# test_instrumentation_amplifier.net
KiCad netlist of a schematic drawn in EAGLE
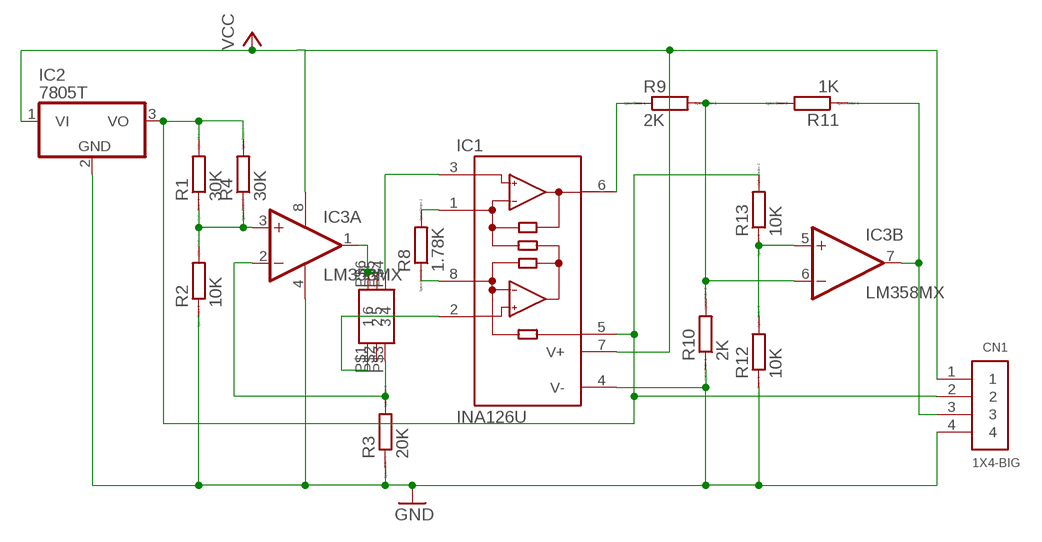
[diagram p0: schematic, sheet 1]

(export (version "E")
  (design (tool "Eeschema 10.0.6"))
  (components
    (comp (ref "CN1")
      (value "1X4-BIG")
      (footprint "eagle-import:1X04-BIG")
      (libsource (lib "eagle-import") (part "1X4-BIG"))
    )
    (comp (ref "IC1")
      (value "INA126U")
      (footprint "eagle-import:SO08")
      (fields (field (name "MF") "Texas Instruments") (field (name "MP") "INA126"))
      (libsource (lib "eagle-import") (part "INA126U"))
    )
    (comp (ref "IC2")
      (value "7805T")
      (footprint "eagle-import:TO220H")
      (fields (field (name "SPICEPREFIX") "X"))
      (libsource (lib "eagle-import") (part "78T05"))
    )
    (comp (ref "IC3")
      (value "LM358MX")
      (footprint "eagle-import:SO08")
      (libsource (lib "eagle-import") (part "LM358MX"))
    )
    (comp (ref "R1")
      (value "30K")
      (footprint "eagle-import:0207_10")
      (libsource (lib "eagle-import") (part "R0207/10"))
    )
    (comp (ref "R2")
      (value "10K")
      (footprint "eagle-import:0207_10")
      (libsource (lib "eagle-import") (part "R0207/10"))
    )
    (comp (ref "R3")
      (value "20K")
      (footprint "eagle-import:0207_10")
      (libsource (lib "eagle-import") (part "R0207/10"))
    )
    (comp (ref "R4")
      (value "30K")
      (footprint "eagle-import:0207_10")
      (libsource (lib "eagle-import") (part "R0207/10"))
    )
    (comp (ref "R8")
      (value "1.78K")
      (footprint "eagle-import:0207_10")
      (libsource (lib "eagle-import") (part "R0207/10"))
    )
    (comp (ref "R9")
      (value "2K")
      (footprint "eagle-import:0207_10")
      (libsource (lib "eagle-import") (part "R0207/10"))
    )
    (comp (ref "R10")
      (value "2K")
      (footprint "eagle-import:0207_10")
      (libsource (lib "eagle-import") (part "R0207/10"))
    )
    (comp (ref "R11")
      (value "1K")
      (footprint "eagle-import:0207_10")
      (libsource (lib "eagle-import") (part "R0207/10"))
    )
    (comp (ref "R12")
      (value "10K")
      (footprint "eagle-import:0207_10")
      (libsource (lib "eagle-import") (part "R0207/10"))
    )
    (comp (ref "R13")
      (value "10K")
      (footprint "eagle-import:0207_10")
      (libsource (lib "eagle-import") (part "R0207/10"))
    )
    (comp (ref "U$1")
      (value "2SMPP-03")
      (footprint "eagle-import:2SMPP-03")
      (libsource (lib "eagle-import") (part "2SMPP-03"))
    )
  )
  (nets
    (net (code "1") (name "GND") (class "Default")
      (node (ref "CN1") (pin "4") (pinfunction "4_4") (pintype "bidirectional"))
      (node (ref "IC1") (pin "4") (pinfunction "V-_4") (pintype "power_in"))
      (node (ref "IC2") (pin "2") (pinfunction "GND_2") (pintype "passive"))
      (node (ref "IC3") (pin "4") (pinfunction "V-_4") (pintype "power_in"))
      (node (ref "R10") (pin "1") (pinfunction "1_1") (pintype "passive"))
      (node (ref "R12") (pin "1") (pinfunction "1_1") (pintype "passive"))
      (node (ref "R2") (pin "1") (pinfunction "1_1") (pintype "passive"))
      (node (ref "R3") (pin "1") (pinfunction "1_1") (pintype "passive"))
    )
    (net (code "2") (name "Net-(IC1-+IN)") (class "Default")
      (node (ref "IC1") (pin "3") (pinfunction "+IN_3") (pintype "input"))
      (node (ref "U$1") (pin "P$4") (pinfunction "4_P$4") (pintype "bidirectional"))
    )
    (net (code "3") (name "Net-(IC1--IN)") (class "Default")
      (node (ref "IC1") (pin "2") (pinfunction "-IN_2") (pintype "input"))
      (node (ref "U$1") (pin "P$1") (pinfunction "1_P$1") (pintype "bidirectional"))
    )
    (net (code "4") (name "Net-(IC1-OUT)") (class "Default")
      (node (ref "IC1") (pin "6") (pinfunction "OUT_6") (pintype "output"))
      (node (ref "R9") (pin "1") (pinfunction "1_1") (pintype "passive"))
    )
    (net (code "5") (name "Net-(IC1-REF)") (class "Default")
      (node (ref "CN1") (pin "2") (pinfunction "2_2") (pintype "bidirectional"))
      (node (ref "IC1") (pin "5") (pinfunction "REF_5") (pintype "passive"))
      (node (ref "IC2") (pin "3") (pinfunction "VO_3") (pintype "passive"))
      (node (ref "R1") (pin "2") (pinfunction "2_2") (pintype "passive"))
      (node (ref "R13") (pin "2") (pinfunction "2_2") (pintype "passive"))
      (node (ref "R4") (pin "2") (pinfunction "2_2") (pintype "passive"))
    )
    (net (code "6") (name "Net-(IC1-RG-Pad1)") (class "Default")
      (node (ref "IC1") (pin "1") (pinfunction "RG_1") (pintype "passive"))
      (node (ref "R8") (pin "2") (pinfunction "2_2") (pintype "passive"))
    )
    (net (code "7") (name "Net-(IC1-RG-Pad8)") (class "Default")
      (node (ref "IC1") (pin "8") (pinfunction "RG_8") (pintype "passive"))
      (node (ref "R8") (pin "1") (pinfunction "1_1") (pintype "passive"))
    )
    (net (code "8") (name "Net-(IC3A-+IN)") (class "Default")
      (node (ref "IC3") (pin "3") (pinfunction "+IN_3") (pintype "input"))
      (node (ref "R1") (pin "1") (pinfunction "1_1") (pintype "passive"))
      (node (ref "R2") (pin "2") (pinfunction "2_2") (pintype "passive"))
      (node (ref "R4") (pin "1") (pinfunction "1_1") (pintype "passive"))
    )
    (net (code "9") (name "Net-(IC3A--IN)") (class "Default")
      (node (ref "IC3") (pin "2") (pinfunction "-IN_2") (pintype "input"))
      (node (ref "R3") (pin "2") (pinfunction "2_2") (pintype "passive"))
      (node (ref "U$1") (pin "P$3") (pinfunction "3_P$3") (pintype "bidirectional"))
    )
    (net (code "10") (name "Net-(IC3A-OUT)") (class "Default")
      (node (ref "IC3") (pin "1") (pinfunction "OUT_1") (pintype "output"))
      (node (ref "U$1") (pin "P$5") (pinfunction "5_P$5") (pintype "bidirectional"))
      (node (ref "U$1") (pin "P$6") (pinfunction "6_P$6") (pintype "bidirectional"))
    )
    (net (code "11") (name "Net-(IC3B-+IN)") (class "Default")
      (node (ref "IC3") (pin "5") (pinfunction "+IN_5") (pintype "input"))
      (node (ref "R12") (pin "2") (pinfunction "2_2") (pintype "passive"))
      (node (ref "R13") (pin "1") (pinfunction "1_1") (pintype "passive"))
    )
    (net (code "12") (name "Net-(IC3B--IN)") (class "Default")
      (node (ref "IC3") (pin "6") (pinfunction "-IN_6") (pintype "input"))
      (node (ref "R10") (pin "2") (pinfunction "2_2") (pintype "passive"))
      (node (ref "R11") (pin "2") (pinfunction "2_2") (pintype "passive"))
      (node (ref "R9") (pin "2") (pinfunction "2_2") (pintype "passive"))
    )
    (net (code "13") (name "Net-(IC3B-OUT)") (class "Default")
      (node (ref "CN1") (pin "3") (pinfunction "3_3") (pintype "bidirectional"))
      (node (ref "IC3") (pin "7") (pinfunction "OUT_7") (pintype "output"))
      (node (ref "R11") (pin "1") (pinfunction "1_1") (pintype "passive"))
    )
    (net (code "14") (name "VCC") (class "Default")
      (node (ref "CN1") (pin "1") (pinfunction "1_1") (pintype "bidirectional"))
      (node (ref "IC1") (pin "7") (pinfunction "V+_7") (pintype "power_in"))
      (node (ref "IC2") (pin "1") (pinfunction "VI_1") (pintype "input"))
      (node (ref "IC3") (pin "8") (pinfunction "V+_8") (pintype "power_in"))
    )
    (net (code "15") (name "unconnected-(U$1-2-PadP$2)") (class "Default")
      (node (ref "U$1") (pin "P$2") (pinfunction "2_P$2") (pintype "bidirectional"))
    )
  )
)
